# piezo-preamp-tickler_V2-RevC.net
KiCad netlist of a schematic drawn in EAGLE
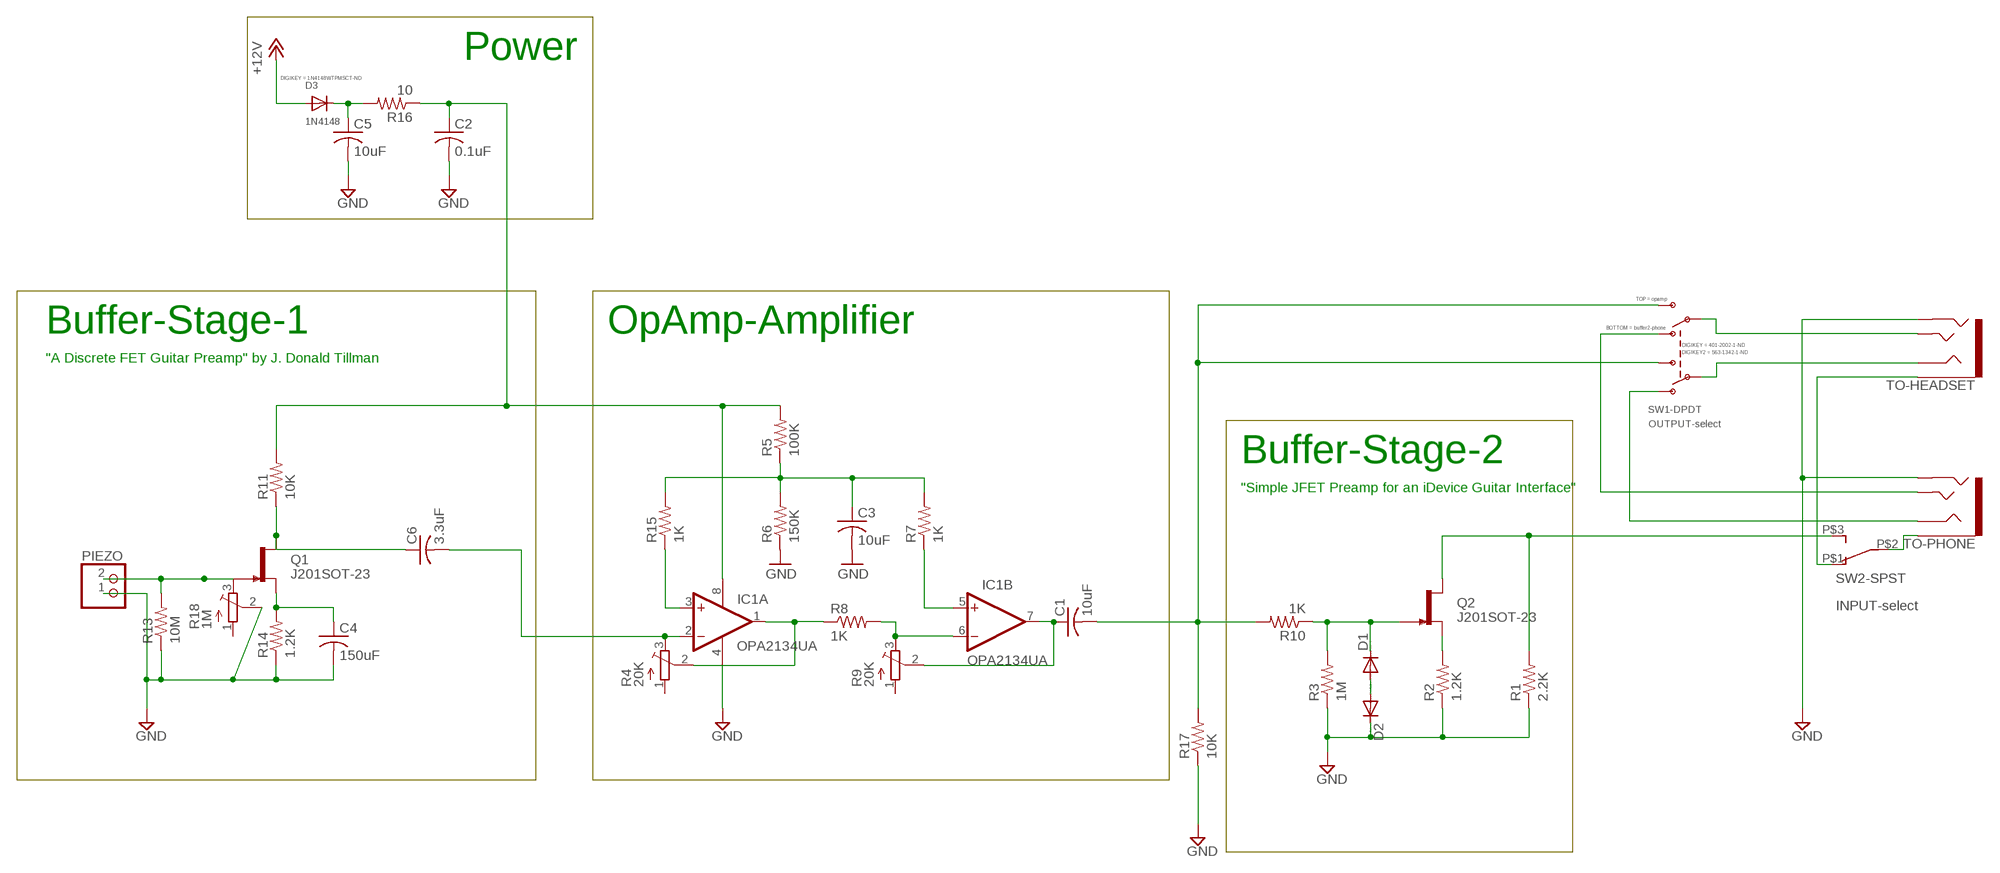
[diagram p0: schematic, sheet 1]
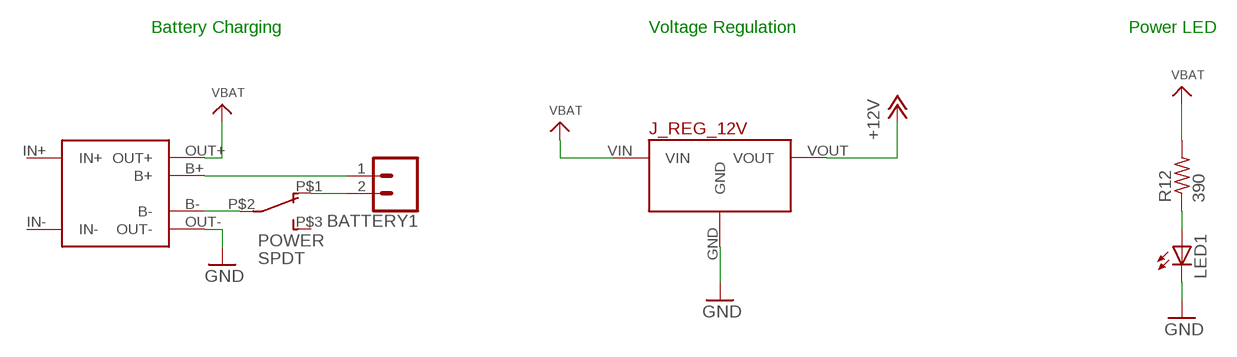
[diagram p1: schematic, sheet 2]

(export (version "E")
  (design (tool "Eeschema 10.0.6"))
  (components
    (comp (ref "C1")
      (value "10uF")
      (footprint "eagle-import:C0805K")
      (libsource (lib "eagle-import") (part "C-USC0805K"))
    )
    (comp (ref "C2")
      (value "0.1uF")
      (footprint "eagle-import:C0805K")
      (libsource (lib "eagle-import") (part "C-USC0805K"))
    )
    (comp (ref "C3")
      (value "10uF")
      (footprint "eagle-import:C0805K")
      (libsource (lib "eagle-import") (part "C-USC0805K"))
    )
    (comp (ref "C4")
      (value "150uF")
      (footprint "eagle-import:C050-024X044")
      (libsource (lib "eagle-import") (part "C-US050-024X044"))
    )
    (comp (ref "C5")
      (value "10uF")
      (footprint "eagle-import:C0805K")
      (libsource (lib "eagle-import") (part "C-USC0805K"))
    )
    (comp (ref "C6")
      (value "3.3uF")
      (footprint "eagle-import:C0805K")
      (libsource (lib "eagle-import") (part "C-USC0805K"))
    )
    (comp (ref "D1")
      (value "DIODE-SOD123")
      (footprint "eagle-import:SOD123")
      (libsource (lib "eagle-import") (part "DIODE-SOD123"))
    )
    (comp (ref "D2")
      (value "DIODE-SOD123")
      (footprint "eagle-import:SOD123")
      (libsource (lib "eagle-import") (part "DIODE-SOD123"))
    )
    (comp (ref "D3")
      (value "1N4148")
      (footprint "eagle-import:SOD-123")
      (fields (field (name "DIGIKEY") "1N4148WTPMSCT-ND"))
      (libsource (lib "eagle-import") (part "DIODESOD-123"))
    )
    (comp (ref "IC1")
      (value "OPA2134UA")
      (footprint "eagle-import:SO08")
      (libsource (lib "eagle-import") (part "OPA2UA134"))
    )
    (comp (ref "PIEZO")
      (value "JST_2PIN-THM")
      (footprint "eagle-import:JST-PH-2-THM")
      (libsource (lib "eagle-import") (part "JST_2PIN-THM"))
    )
    (comp (ref "Q1")
      (value "J201SOT-23")
      (footprint "eagle-import:SOT23-3")
      (libsource (lib "eagle-import") (part "J201SOT-23"))
    )
    (comp (ref "Q2")
      (value "J201SOT-23")
      (footprint "eagle-import:SOT23-3")
      (libsource (lib "eagle-import") (part "J201SOT-23"))
    )
    (comp (ref "R1")
      (value "2.2K")
      (footprint "eagle-import:R0603")
      (libsource (lib "eagle-import") (part "R-US_R0603"))
    )
    (comp (ref "R2")
      (value "1.2K")
      (footprint "eagle-import:R0603")
      (libsource (lib "eagle-import") (part "R-US_R0603"))
    )
    (comp (ref "R3")
      (value "1M")
      (footprint "eagle-import:R0603")
      (libsource (lib "eagle-import") (part "R-US_R0603"))
    )
    (comp (ref "R4")
      (value "20K")
      (footprint "eagle-import:TC33X")
      (libsource (lib "eagle-import") (part "TRIMPOTTC33X"))
    )
    (comp (ref "R5")
      (value "100K")
      (footprint "eagle-import:R0603")
      (libsource (lib "eagle-import") (part "R-US_R0603"))
    )
    (comp (ref "R6")
      (value "150K")
      (footprint "eagle-import:R0603")
      (libsource (lib "eagle-import") (part "R-US_R0603"))
    )
    (comp (ref "R7")
      (value "1K")
      (footprint "eagle-import:R0603")
      (libsource (lib "eagle-import") (part "R-US_R0603"))
    )
    (comp (ref "R8")
      (value "1K")
      (footprint "eagle-import:R0603")
      (libsource (lib "eagle-import") (part "R-US_R0603"))
    )
    (comp (ref "R9")
      (value "20K")
      (footprint "eagle-import:TC33X")
      (libsource (lib "eagle-import") (part "TRIMPOTTC33X"))
    )
    (comp (ref "R10")
      (value "1K")
      (footprint "eagle-import:R0603")
      (libsource (lib "eagle-import") (part "R-US_R0603"))
    )
    (comp (ref "R11")
      (value "10K")
      (footprint "eagle-import:R0603")
      (libsource (lib "eagle-import") (part "R-US_R0603"))
    )
    (comp (ref "R13")
      (value "10M")
      (footprint "eagle-import:R0603")
      (libsource (lib "eagle-import") (part "R-US_R0603"))
    )
    (comp (ref "R14")
      (value "1.2K")
      (footprint "eagle-import:R0603")
      (libsource (lib "eagle-import") (part "R-US_R0603"))
    )
    (comp (ref "R15")
      (value "1K")
      (footprint "eagle-import:R0603")
      (libsource (lib "eagle-import") (part "R-US_R0603"))
    )
    (comp (ref "R16")
      (value "10")
      (footprint "eagle-import:R0603")
      (libsource (lib "eagle-import") (part "R-US_R0603"))
    )
    (comp (ref "R17")
      (value "10K")
      (footprint "eagle-import:R0603")
      (libsource (lib "eagle-import") (part "R-US_R0603"))
    )
    (comp (ref "R18")
      (value "1M")
      (footprint "eagle-import:TC33X")
      (libsource (lib "eagle-import") (part "TRIMPOTTC33X"))
    )
    (comp (ref "SW1-DPDT")
      (value "OUTPUT-select")
      (footprint "eagle-import:DPDT_SMT_JS202011SCQN")
      (fields
        (field (name "BOTTOM") "buffer2-phone")
        (field (name "DIGIKEY") "401-2002-1-ND")
        (field (name "DIGIKEY2") "563-1342-1-ND")
        (field (name "TOP") "opamp")
      )
      (libsource (lib "eagle-import") (part "SWITCH_DPDT"))
    )
    (comp (ref "SW2-SPST")
      (value "INPUT-select")
      (footprint "eagle-import:SWITCH_SPDT_CL-SB-12B")
      (libsource (lib "eagle-import") (part "SWITCH_SPDTCL-SB-12B"))
    )
    (comp (ref "TO-HEADSET")
      (value "AUDIO-JACK3LGPADS")
      (footprint "eagle-import:AUDIO-JACK-TRRS-SMD")
      (libsource (lib "eagle-import") (part "AUDIO-JACK3LGPADS"))
    )
    (comp (ref "TO-PHONE")
      (value "AUDIO-JACK3LGPADS")
      (footprint "eagle-import:AUDIO-JACK-TRRS-SMD")
      (libsource (lib "eagle-import") (part "AUDIO-JACK3LGPADS"))
    )
    (comp (ref "BATTERY1")
      (value "CONN_02LOCK")
      (footprint "eagle-import:1X02_LOCK")
      (libsource (lib "eagle-import") (part "CONN_02LOCK"))
    )
    (comp (ref "J_REG_12V")
      (value "POLOLU_VOLTAGE_REGULATORS_3PIN")
      (footprint "eagle-import:POLOLU_5V-12V_STEPUP_U3V12F5-U3V12F12")
      (libsource (lib "eagle-import") (part "POLOLU_VOLTAGE_REGULATORS_3PIN"))
    )
    (comp (ref "LED1")
      (value "LED3MM")
      (footprint "eagle-import:LED3MM")
      (libsource (lib "eagle-import") (part "LED3MM"))
    )
    (comp (ref "POWER")
      (value "SPDT")
      (footprint "eagle-import:SWITCH_SPDT_CL-SB-12B")
      (libsource (lib "eagle-import") (part "SWITCH_SPDTCL-SB-12B"))
    )
    (comp (ref "R12")
      (value "390")
      (footprint "eagle-import:R0805")
      (libsource (lib "eagle-import") (part "R-US_R0805"))
    )
    (comp (ref "USB-LIPO-CHARGER")
      (value "TP4056-MODULE")
      (footprint "eagle-import:TP4056-LITHIUM-PROTECTED-MODULE")
      (libsource (lib "eagle-import") (part "TP4056-MODULE"))
    )
  )
  (nets
    (net (code "1") (name "+12V") (class "Default")
      (node (ref "D3") (pin "A") (pinfunction "A_A") (pintype "passive"))
      (node (ref "J_REG_12V") (pin "VOUT") (pinfunction "VOUT_VOUT") (pintype "bidirectional"))
    )
    (net (code "2") (name "GND") (class "Default")
      (node (ref "C2") (pin "2") (pinfunction "2_2") (pintype "passive"))
      (node (ref "C3") (pin "2") (pinfunction "2_2") (pintype "passive"))
      (node (ref "C4") (pin "2") (pinfunction "2_2") (pintype "passive"))
      (node (ref "C5") (pin "2") (pinfunction "2_2") (pintype "passive"))
      (node (ref "D2") (pin "C") (pinfunction "C_C") (pintype "passive"))
      (node (ref "IC1") (pin "4") (pinfunction "V-_4") (pintype "power_in"))
      (node (ref "J_REG_12V") (pin "GND") (pinfunction "GND_GND") (pintype "bidirectional"))
      (node (ref "LED1") (pin "K") (pinfunction "C_K") (pintype "passive"))
      (node (ref "PIEZO") (pin "1") (pinfunction "2_1") (pintype "passive"))
      (node (ref "R1") (pin "1") (pinfunction "1_1") (pintype "passive"))
      (node (ref "R13") (pin "1") (pinfunction "1_1") (pintype "passive"))
      (node (ref "R14") (pin "1") (pinfunction "1_1") (pintype "passive"))
      (node (ref "R17") (pin "1") (pinfunction "1_1") (pintype "passive"))
      (node (ref "R18") (pin "2") (pinfunction "S_2") (pintype "passive"))
      (node (ref "R2") (pin "1") (pinfunction "1_1") (pintype "passive"))
      (node (ref "R3") (pin "1") (pinfunction "1_1") (pintype "passive"))
      (node (ref "R6") (pin "1") (pinfunction "1_1") (pintype "passive"))
      (node (ref "TO-HEADSET") (pin "RING2") (pinfunction "RING2_RING2") (pintype "bidirectional"))
      (node (ref "TO-PHONE") (pin "RING2") (pinfunction "RING2_RING2") (pintype "bidirectional"))
      (node (ref "USB-LIPO-CHARGER") (pin "OUT-") (pinfunction "OUT-_OUT-") (pintype "power_in"))
    )
    (net (code "3") (name "IN+") (class "Default")
      (node (ref "USB-LIPO-CHARGER") (pin "IN+") (pinfunction "IN+_IN+") (pintype "power_in"))
    )
    (net (code "4") (name "IN-") (class "Default")
      (node (ref "USB-LIPO-CHARGER") (pin "IN-") (pinfunction "IN-_IN-") (pintype "power_in"))
    )
    (net (code "5") (name "Net-(BATTERY1-Pad1)") (class "Default")
      (node (ref "BATTERY1") (pin "1") (pinfunction "1_1") (pintype "passive"))
      (node (ref "USB-LIPO-CHARGER") (pin "B+") (pinfunction "B+_B+") (pintype "power_in"))
    )
    (net (code "6") (name "Net-(C3-Pad1)") (class "Default")
      (node (ref "C3") (pin "1") (pinfunction "1_1") (pintype "passive"))
      (node (ref "R15") (pin "2") (pinfunction "2_2") (pintype "passive"))
      (node (ref "R5") (pin "1") (pinfunction "1_1") (pintype "passive"))
      (node (ref "R6") (pin "2") (pinfunction "2_2") (pintype "passive"))
      (node (ref "R7") (pin "2") (pinfunction "2_2") (pintype "passive"))
    )
    (net (code "7") (name "Net-(C5-Pad1)") (class "Default")
      (node (ref "C5") (pin "1") (pinfunction "1_1") (pintype "passive"))
      (node (ref "D3") (pin "C") (pinfunction "C_C") (pintype "passive"))
      (node (ref "R16") (pin "2") (pinfunction "2_2") (pintype "passive"))
    )
    (net (code "8") (name "Net-(D1-PadA)") (class "Default")
      (node (ref "D1") (pin "A") (pinfunction "A_A") (pintype "passive"))
      (node (ref "D2") (pin "A") (pinfunction "A_A") (pintype "passive"))
    )
    (net (code "9") (name "Net-(IC1A-+IN)") (class "Default")
      (node (ref "IC1") (pin "3") (pinfunction "+IN_3") (pintype "input"))
      (node (ref "R15") (pin "1") (pinfunction "1_1") (pintype "passive"))
    )
    (net (code "10") (name "Net-(IC1A--IN)") (class "Default")
      (node (ref "C6") (pin "2") (pinfunction "2_2") (pintype "passive"))
      (node (ref "IC1") (pin "2") (pinfunction "-IN_2") (pintype "input"))
      (node (ref "R4") (pin "3") (pinfunction "E_3") (pintype "passive"))
    )
    (net (code "11") (name "Net-(IC1A-OUT)") (class "Default")
      (node (ref "IC1") (pin "1") (pinfunction "OUT_1") (pintype "output"))
      (node (ref "R4") (pin "2") (pinfunction "S_2") (pintype "passive"))
      (node (ref "R8") (pin "1") (pinfunction "1_1") (pintype "passive"))
    )
    (net (code "12") (name "Net-(IC1A-V+)") (class "Default")
      (node (ref "C2") (pin "1") (pinfunction "1_1") (pintype "passive"))
      (node (ref "IC1") (pin "8") (pinfunction "V+_8") (pintype "power_in"))
      (node (ref "R11") (pin "2") (pinfunction "2_2") (pintype "passive"))
      (node (ref "R16") (pin "1") (pinfunction "1_1") (pintype "passive"))
      (node (ref "R5") (pin "2") (pinfunction "2_2") (pintype "passive"))
    )
    (net (code "13") (name "Net-(IC1B-+IN)") (class "Default")
      (node (ref "IC1") (pin "5") (pinfunction "+IN_5") (pintype "input"))
      (node (ref "R7") (pin "1") (pinfunction "1_1") (pintype "passive"))
    )
    (net (code "14") (name "Net-(IC1B--IN)") (class "Default")
      (node (ref "IC1") (pin "6") (pinfunction "-IN_6") (pintype "input"))
      (node (ref "R8") (pin "2") (pinfunction "2_2") (pintype "passive"))
      (node (ref "R9") (pin "3") (pinfunction "E_3") (pintype "passive"))
    )
    (net (code "15") (name "Net-(IC1B-OUT)") (class "Default")
      (node (ref "C1") (pin "1") (pinfunction "1_1") (pintype "passive"))
      (node (ref "IC1") (pin "7") (pinfunction "OUT_7") (pintype "output"))
      (node (ref "R9") (pin "2") (pinfunction "S_2") (pintype "passive"))
    )
    (net (code "16") (name "Net-(LED1-PadA)") (class "Default")
      (node (ref "LED1") (pin "A") (pinfunction "A_A") (pintype "passive"))
      (node (ref "R12") (pin "1") (pinfunction "1_1") (pintype "passive"))
    )
    (net (code "17") (name "Net-(PIEZO-1)") (class "Default")
      (node (ref "PIEZO") (pin "2") (pinfunction "1_2") (pintype "passive"))
      (node (ref "Q1") (pin "3") (pinfunction "G_3") (pintype "passive"))
      (node (ref "R13") (pin "2") (pinfunction "2_2") (pintype "passive"))
      (node (ref "R18") (pin "3") (pinfunction "E_3") (pintype "passive"))
    )
    (net (code "18") (name "Net-(POWER-1)") (class "Default")
      (node (ref "BATTERY1") (pin "2") (pinfunction "2_2") (pintype "passive"))
      (node (ref "POWER") (pin "P$1") (pinfunction "1_P$1") (pintype "passive"))
    )
    (net (code "19") (name "Net-(POWER-2)") (class "Default")
      (node (ref "POWER") (pin "P$2") (pinfunction "2_P$2") (pintype "passive"))
      (node (ref "USB-LIPO-CHARGER") (pin "B-") (pinfunction "B-_B-") (pintype "power_in"))
    )
    (net (code "20") (name "Net-(Q1-D)") (class "Default")
      (node (ref "C6") (pin "1") (pinfunction "1_1") (pintype "passive"))
      (node (ref "Q1") (pin "1") (pinfunction "D_1") (pintype "passive"))
      (node (ref "R11") (pin "1") (pinfunction "1_1") (pintype "passive"))
    )
    (net (code "21") (name "Net-(Q1-S)") (class "Default")
      (node (ref "C4") (pin "1") (pinfunction "1_1") (pintype "passive"))
      (node (ref "Q1") (pin "2") (pinfunction "S_2") (pintype "passive"))
      (node (ref "R14") (pin "2") (pinfunction "2_2") (pintype "passive"))
    )
    (net (code "22") (name "Net-(Q2-D)") (class "Default")
      (node (ref "Q2") (pin "1") (pinfunction "D_1") (pintype "passive"))
      (node (ref "R1") (pin "2") (pinfunction "2_2") (pintype "passive"))
      (node (ref "SW2-SPST") (pin "P$3") (pinfunction "3_P$3") (pintype "passive"))
    )
    (net (code "23") (name "Net-(Q2-G)") (class "Default")
      (node (ref "D1") (pin "C") (pinfunction "C_C") (pintype "passive"))
      (node (ref "Q2") (pin "3") (pinfunction "G_3") (pintype "passive"))
      (node (ref "R10") (pin "1") (pinfunction "1_1") (pintype "passive"))
      (node (ref "R3") (pin "2") (pinfunction "2_2") (pintype "passive"))
    )
    (net (code "24") (name "Net-(Q2-S)") (class "Default")
      (node (ref "Q2") (pin "2") (pinfunction "S_2") (pintype "passive"))
      (node (ref "R2") (pin "2") (pinfunction "2_2") (pintype "passive"))
    )
    (net (code "25") (name "Net-(SW1-DPDT-O1)") (class "Default")
      (node (ref "SW1-DPDT") (pin "P$1") (pinfunction "O1_P$1") (pintype "passive"))
      (node (ref "TO-PHONE") (pin "RING1") (pinfunction "RING1_RING1") (pintype "bidirectional"))
    )
    (net (code "26") (name "Net-(SW1-DPDT-O2)") (class "Default")
      (node (ref "SW1-DPDT") (pin "P$6") (pinfunction "O2_P$6") (pintype "passive"))
      (node (ref "TO-PHONE") (pin "TIP") (pinfunction "TIP_TIP") (pintype "bidirectional"))
    )
    (net (code "27") (name "Net-(SW1-DPDT-P1)") (class "Default")
      (node (ref "SW1-DPDT") (pin "P$2") (pinfunction "P1_P$2") (pintype "passive"))
      (node (ref "TO-HEADSET") (pin "RING1") (pinfunction "RING1_RING1") (pintype "bidirectional"))
    )
    (net (code "28") (name "Net-(SW1-DPDT-P2)") (class "Default")
      (node (ref "SW1-DPDT") (pin "P$5") (pinfunction "P2_P$5") (pintype "passive"))
      (node (ref "TO-HEADSET") (pin "TIP") (pinfunction "TIP_TIP") (pintype "bidirectional"))
    )
    (net (code "29") (name "Net-(SW1-DPDT-S1)") (class "Default")
      (node (ref "C1") (pin "2") (pinfunction "2_2") (pintype "passive"))
      (node (ref "R10") (pin "2") (pinfunction "2_2") (pintype "passive"))
      (node (ref "R17") (pin "2") (pinfunction "2_2") (pintype "passive"))
      (node (ref "SW1-DPDT") (pin "P$3") (pinfunction "S1_P$3") (pintype "passive"))
      (node (ref "SW1-DPDT") (pin "P$4") (pinfunction "S2_P$4") (pintype "passive"))
    )
    (net (code "30") (name "Net-(SW2-SPST-1)") (class "Default")
      (node (ref "SW2-SPST") (pin "P$1") (pinfunction "1_P$1") (pintype "passive"))
      (node (ref "TO-HEADSET") (pin "EARTH") (pinfunction "EARTH_EARTH") (pintype "bidirectional"))
    )
    (net (code "31") (name "Net-(SW2-SPST-2)") (class "Default")
      (node (ref "SW2-SPST") (pin "P$2") (pinfunction "2_P$2") (pintype "passive"))
      (node (ref "TO-PHONE") (pin "EARTH") (pinfunction "EARTH_EARTH") (pintype "bidirectional"))
    )
    (net (code "32") (name "VBAT") (class "Default")
      (node (ref "J_REG_12V") (pin "VIN") (pinfunction "VIN_VIN") (pintype "bidirectional"))
      (node (ref "R12") (pin "2") (pinfunction "2_2") (pintype "passive"))
      (node (ref "USB-LIPO-CHARGER") (pin "OUT+") (pinfunction "OUT+_OUT+") (pintype "power_in"))
    )
    (net (code "33") (name "unconnected-(POWER-3-PadP$3)") (class "Default")
      (node (ref "POWER") (pin "P$3") (pinfunction "3_P$3") (pintype "passive"))
    )
    (net (code "34") (name "unconnected-(R4-A-Pad1)") (class "Default")
      (node (ref "R4") (pin "1") (pinfunction "A_1") (pintype "passive"))
    )
    (net (code "35") (name "unconnected-(R9-A-Pad1)") (class "Default")
      (node (ref "R9") (pin "1") (pinfunction "A_1") (pintype "passive"))
    )
    (net (code "36") (name "unconnected-(R18-A-Pad1)") (class "Default")
      (node (ref "R18") (pin "1") (pinfunction "A_1") (pintype "passive"))
    )
  )
)
